# ZEROCROSS_ATmega328.net
KiCad netlist of a schematic drawn in EAGLE
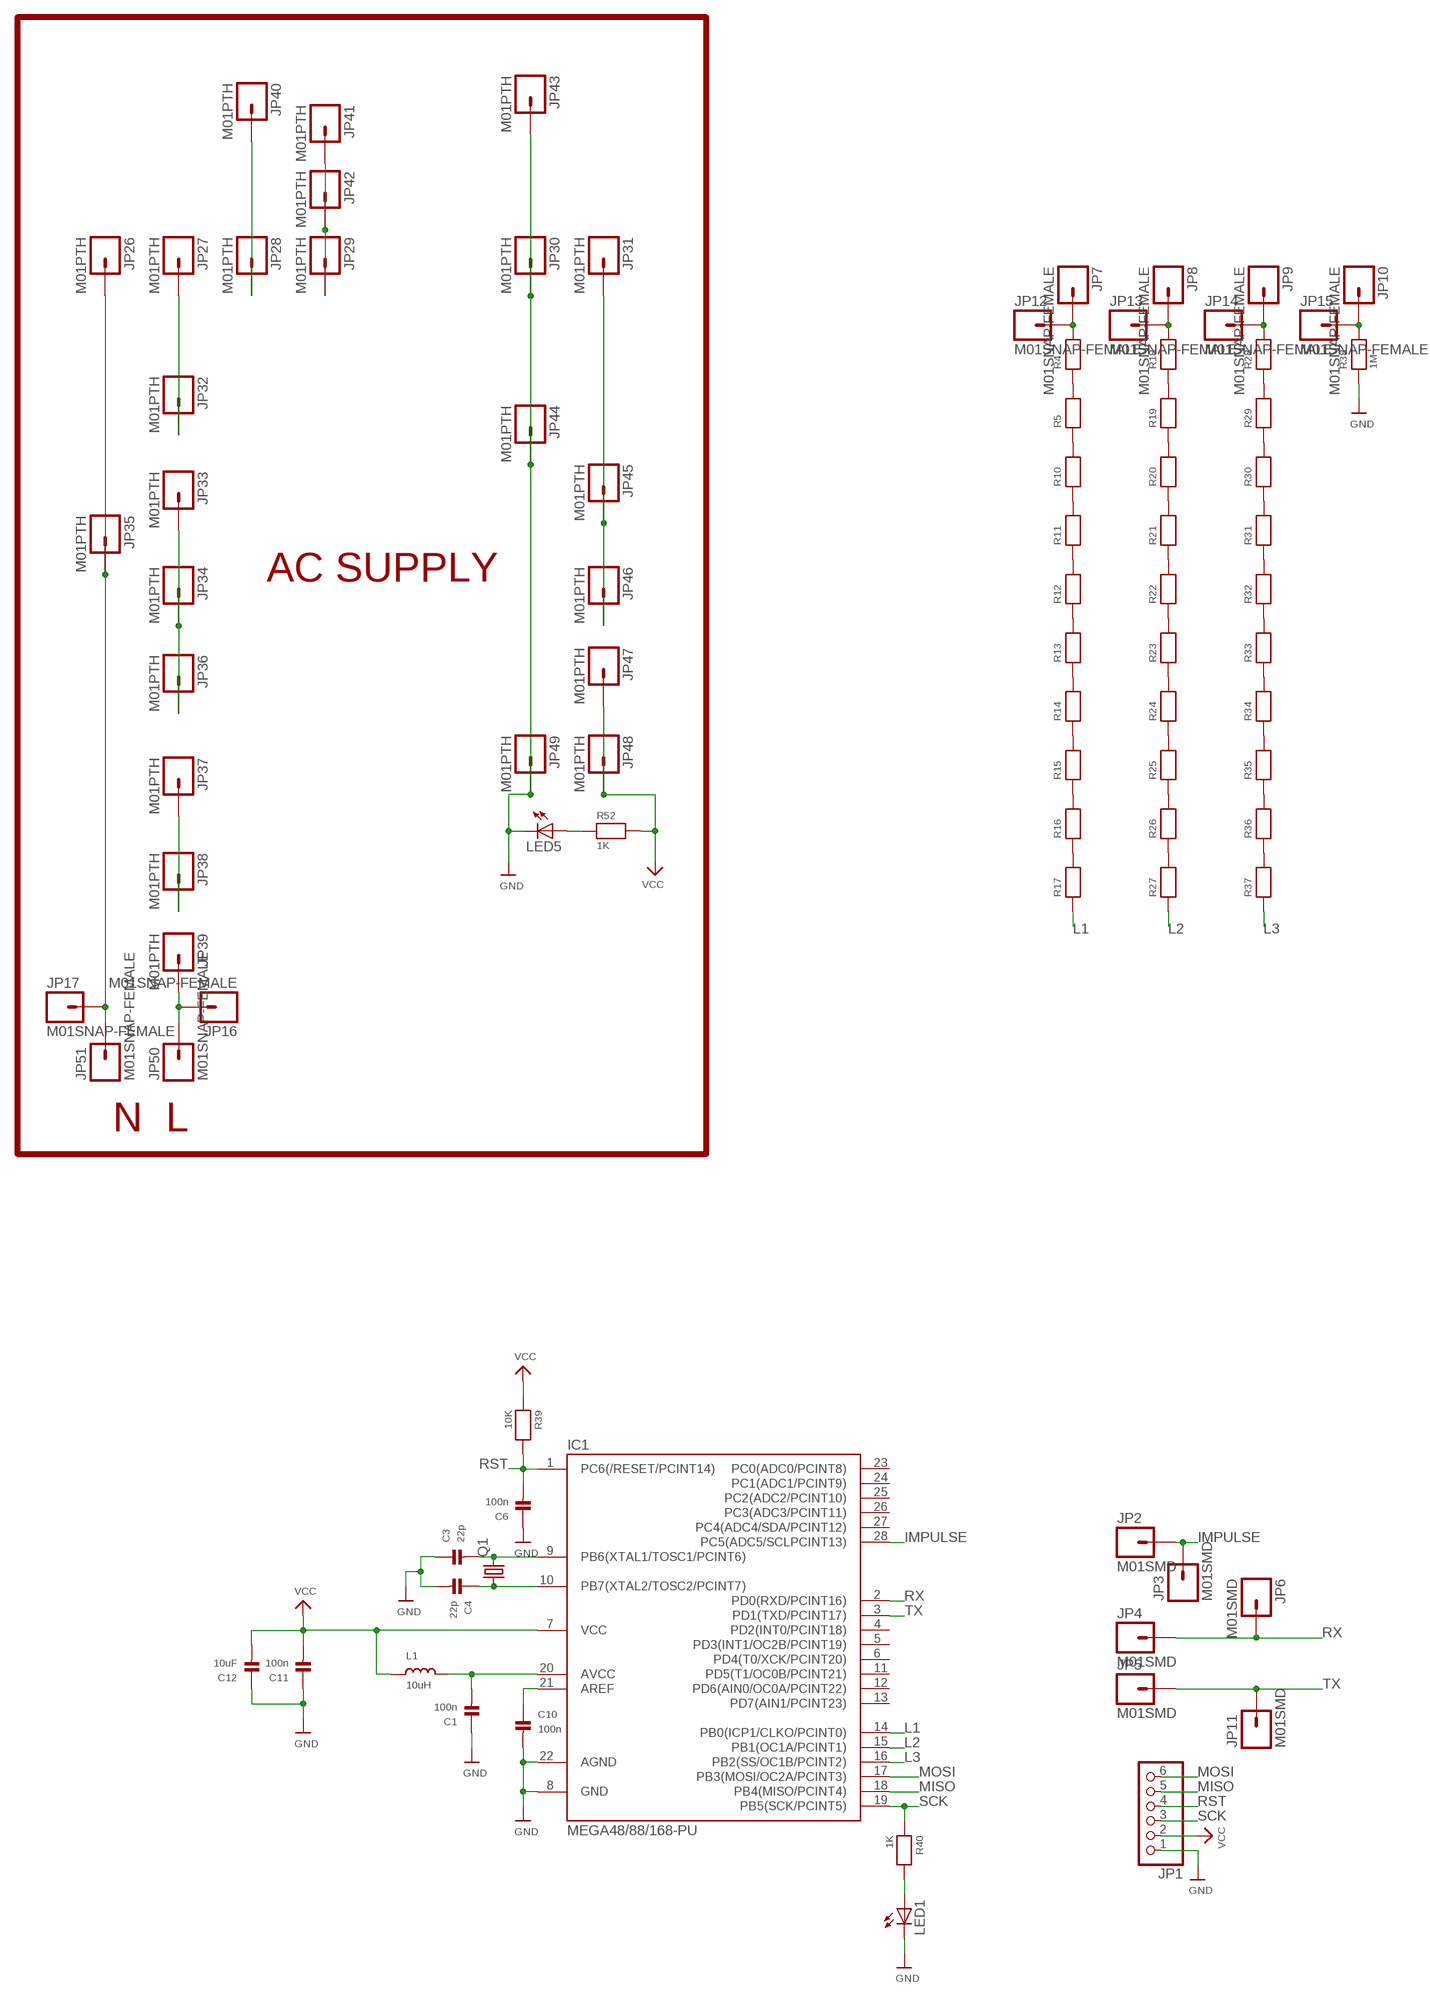
[diagram p0: schematic, sheet 1]

(export (version "E")
  (design (tool "Eeschema 10.0.6"))
  (components
    (comp (ref "C1")
      (value "100n")
      (footprint "eagle-import:_0805MP")
      (libsource (lib "eagle-import") (part "CAP_CERAMIC_0805MP"))
    )
    (comp (ref "C3")
      (value "22p")
      (footprint "eagle-import:_0805MP")
      (libsource (lib "eagle-import") (part "CAP_CERAMIC_0805MP"))
    )
    (comp (ref "C4")
      (value "22p")
      (footprint "eagle-import:_0805MP")
      (libsource (lib "eagle-import") (part "CAP_CERAMIC_0805MP"))
    )
    (comp (ref "C6")
      (value "100n")
      (footprint "eagle-import:_0805MP")
      (libsource (lib "eagle-import") (part "CAP_CERAMIC_0805MP"))
    )
    (comp (ref "C10")
      (value "100n")
      (footprint "eagle-import:_0805MP")
      (libsource (lib "eagle-import") (part "CAP_CERAMIC_0805MP"))
    )
    (comp (ref "C11")
      (value "100n")
      (footprint "eagle-import:_0805MP")
      (libsource (lib "eagle-import") (part "CAP_CERAMIC_0805MP"))
    )
    (comp (ref "C12")
      (value "10uF")
      (footprint "eagle-import:_0805MP")
      (libsource (lib "eagle-import") (part "CAP_CERAMIC_0805MP"))
    )
    (comp (ref "IC1")
      (value "MEGA48/88/168-PU")
      (footprint "eagle-import:DIL28-3")
      (libsource (lib "eagle-import") (part "MEGA48/88/168-PU"))
    )
    (comp (ref "JP1")
      (value "HEADER-1X6")
      (footprint "eagle-import:1X06_OVAL")
      (libsource (lib "eagle-import") (part "HEADER-1X6"))
    )
    (comp (ref "JP2")
      (value "M01SMD")
      (footprint "eagle-import:LUXEON-PAD")
      (libsource (lib "eagle-import") (part "M01SMD"))
    )
    (comp (ref "JP3")
      (value "M01SMD")
      (footprint "eagle-import:LUXEON-PAD")
      (libsource (lib "eagle-import") (part "M01SMD"))
    )
    (comp (ref "JP4")
      (value "M01SMD")
      (footprint "eagle-import:LUXEON-PAD")
      (libsource (lib "eagle-import") (part "M01SMD"))
    )
    (comp (ref "JP5")
      (value "M01SMD")
      (footprint "eagle-import:LUXEON-PAD")
      (libsource (lib "eagle-import") (part "M01SMD"))
    )
    (comp (ref "JP6")
      (value "M01SMD")
      (footprint "eagle-import:LUXEON-PAD")
      (libsource (lib "eagle-import") (part "M01SMD"))
    )
    (comp (ref "JP7")
      (value "M01SNAP-FEMALE")
      (footprint "eagle-import:SNAP-FEMALE")
      (libsource (lib "eagle-import") (part "M01SNAP-FEMALE"))
    )
    (comp (ref "JP8")
      (value "M01SNAP-FEMALE")
      (footprint "eagle-import:SNAP-FEMALE")
      (libsource (lib "eagle-import") (part "M01SNAP-FEMALE"))
    )
    (comp (ref "JP9")
      (value "M01SNAP-FEMALE")
      (footprint "eagle-import:SNAP-FEMALE")
      (libsource (lib "eagle-import") (part "M01SNAP-FEMALE"))
    )
    (comp (ref "JP10")
      (value "M01SNAP-FEMALE")
      (footprint "eagle-import:SNAP-FEMALE")
      (libsource (lib "eagle-import") (part "M01SNAP-FEMALE"))
    )
    (comp (ref "JP11")
      (value "M01SMD")
      (footprint "eagle-import:LUXEON-PAD")
      (libsource (lib "eagle-import") (part "M01SMD"))
    )
    (comp (ref "JP12")
      (value "M01SNAP-FEMALE")
      (footprint "eagle-import:SNAP-FEMALE")
      (libsource (lib "eagle-import") (part "M01SNAP-FEMALE"))
    )
    (comp (ref "JP13")
      (value "M01SNAP-FEMALE")
      (footprint "eagle-import:SNAP-FEMALE")
      (libsource (lib "eagle-import") (part "M01SNAP-FEMALE"))
    )
    (comp (ref "JP14")
      (value "M01SNAP-FEMALE")
      (footprint "eagle-import:SNAP-FEMALE")
      (libsource (lib "eagle-import") (part "M01SNAP-FEMALE"))
    )
    (comp (ref "JP15")
      (value "M01SNAP-FEMALE")
      (footprint "eagle-import:SNAP-FEMALE")
      (libsource (lib "eagle-import") (part "M01SNAP-FEMALE"))
    )
    (comp (ref "JP16")
      (value "M01SNAP-FEMALE")
      (footprint "eagle-import:SNAP-FEMALE")
      (libsource (lib "eagle-import") (part "M01SNAP-FEMALE"))
    )
    (comp (ref "JP17")
      (value "M01SNAP-FEMALE")
      (footprint "eagle-import:SNAP-FEMALE")
      (libsource (lib "eagle-import") (part "M01SNAP-FEMALE"))
    )
    (comp (ref "JP26")
      (value "M01PTH")
      (footprint "eagle-import:1X01")
      (libsource (lib "eagle-import") (part "M01PTH"))
    )
    (comp (ref "JP27")
      (value "M01PTH")
      (footprint "eagle-import:1X01")
      (libsource (lib "eagle-import") (part "M01PTH"))
    )
    (comp (ref "JP28")
      (value "M01PTH")
      (footprint "eagle-import:1X01")
      (libsource (lib "eagle-import") (part "M01PTH"))
    )
    (comp (ref "JP29")
      (value "M01PTH")
      (footprint "eagle-import:1X01")
      (libsource (lib "eagle-import") (part "M01PTH"))
    )
    (comp (ref "JP30")
      (value "M01PTH")
      (footprint "eagle-import:1X01")
      (libsource (lib "eagle-import") (part "M01PTH"))
    )
    (comp (ref "JP31")
      (value "M01PTH")
      (footprint "eagle-import:1X01")
      (libsource (lib "eagle-import") (part "M01PTH"))
    )
    (comp (ref "JP32")
      (value "M01PTH")
      (footprint "eagle-import:1X01")
      (libsource (lib "eagle-import") (part "M01PTH"))
    )
    (comp (ref "JP33")
      (value "M01PTH")
      (footprint "eagle-import:1X01")
      (libsource (lib "eagle-import") (part "M01PTH"))
    )
    (comp (ref "JP34")
      (value "M01PTH")
      (footprint "eagle-import:1X01")
      (libsource (lib "eagle-import") (part "M01PTH"))
    )
    (comp (ref "JP35")
      (value "M01PTH")
      (footprint "eagle-import:1X01")
      (libsource (lib "eagle-import") (part "M01PTH"))
    )
    (comp (ref "JP36")
      (value "M01PTH")
      (footprint "eagle-import:1X01")
      (libsource (lib "eagle-import") (part "M01PTH"))
    )
    (comp (ref "JP37")
      (value "M01PTH")
      (footprint "eagle-import:1X01")
      (libsource (lib "eagle-import") (part "M01PTH"))
    )
    (comp (ref "JP38")
      (value "M01PTH")
      (footprint "eagle-import:1X01")
      (libsource (lib "eagle-import") (part "M01PTH"))
    )
    (comp (ref "JP39")
      (value "M01PTH")
      (footprint "eagle-import:1X01")
      (libsource (lib "eagle-import") (part "M01PTH"))
    )
    (comp (ref "JP40")
      (value "M01PTH")
      (footprint "eagle-import:1X01")
      (libsource (lib "eagle-import") (part "M01PTH"))
    )
    (comp (ref "JP41")
      (value "M01PTH")
      (footprint "eagle-import:1X01")
      (libsource (lib "eagle-import") (part "M01PTH"))
    )
    (comp (ref "JP42")
      (value "M01PTH")
      (footprint "eagle-import:1X01")
      (libsource (lib "eagle-import") (part "M01PTH"))
    )
    (comp (ref "JP43")
      (value "M01PTH")
      (footprint "eagle-import:1X01")
      (libsource (lib "eagle-import") (part "M01PTH"))
    )
    (comp (ref "JP44")
      (value "M01PTH")
      (footprint "eagle-import:1X01")
      (libsource (lib "eagle-import") (part "M01PTH"))
    )
    (comp (ref "JP45")
      (value "M01PTH")
      (footprint "eagle-import:1X01")
      (libsource (lib "eagle-import") (part "M01PTH"))
    )
    (comp (ref "JP46")
      (value "M01PTH")
      (footprint "eagle-import:1X01")
      (libsource (lib "eagle-import") (part "M01PTH"))
    )
    (comp (ref "JP47")
      (value "M01PTH")
      (footprint "eagle-import:1X01")
      (libsource (lib "eagle-import") (part "M01PTH"))
    )
    (comp (ref "JP48")
      (value "M01PTH")
      (footprint "eagle-import:1X01")
      (libsource (lib "eagle-import") (part "M01PTH"))
    )
    (comp (ref "JP49")
      (value "M01PTH")
      (footprint "eagle-import:1X01")
      (libsource (lib "eagle-import") (part "M01PTH"))
    )
    (comp (ref "JP50")
      (value "M01SNAP-FEMALE")
      (footprint "eagle-import:SNAP-FEMALE")
      (libsource (lib "eagle-import") (part "M01SNAP-FEMALE"))
    )
    (comp (ref "JP51")
      (value "M01SNAP-FEMALE")
      (footprint "eagle-import:SNAP-FEMALE")
      (libsource (lib "eagle-import") (part "M01SNAP-FEMALE"))
    )
    (comp (ref "L1")
      (value "10uH")
      (footprint "eagle-import:_0805MP")
      (libsource (lib "eagle-import") (part "INDUCTOR_0805MP"))
    )
    (comp (ref "LED1")
      (value "LED-3MM-NO_SILK")
      (footprint "eagle-import:LED3MM-NS")
      (libsource (lib "eagle-import") (part "LED-3MM-NO_SILK"))
    )
    (comp (ref "LED5")
      (value "LED-3MM-NO_SILK")
      (footprint "eagle-import:LED3MM-NS")
      (libsource (lib "eagle-import") (part "LED-3MM-NO_SILK"))
    )
    (comp (ref "Q1")
      (value "CRYSTALHC49U-V")
      (footprint "eagle-import:HC49U-V")
      (libsource (lib "eagle-import") (part "CRYSTALHC49U-V"))
    )
    (comp (ref "R4")
      (value "RESISTOR1206")
      (footprint "eagle-import:1206")
      (libsource (lib "eagle-import") (part "RESISTOR1206"))
    )
    (comp (ref "R5")
      (value "RESISTOR1206")
      (footprint "eagle-import:1206")
      (libsource (lib "eagle-import") (part "RESISTOR1206"))
    )
    (comp (ref "R10")
      (value "RESISTOR1206")
      (footprint "eagle-import:1206")
      (libsource (lib "eagle-import") (part "RESISTOR1206"))
    )
    (comp (ref "R11")
      (value "RESISTOR1206")
      (footprint "eagle-import:1206")
      (libsource (lib "eagle-import") (part "RESISTOR1206"))
    )
    (comp (ref "R12")
      (value "RESISTOR1206")
      (footprint "eagle-import:1206")
      (libsource (lib "eagle-import") (part "RESISTOR1206"))
    )
    (comp (ref "R13")
      (value "RESISTOR1206")
      (footprint "eagle-import:1206")
      (libsource (lib "eagle-import") (part "RESISTOR1206"))
    )
    (comp (ref "R14")
      (value "RESISTOR1206")
      (footprint "eagle-import:1206")
      (libsource (lib "eagle-import") (part "RESISTOR1206"))
    )
    (comp (ref "R15")
      (value "RESISTOR1206")
      (footprint "eagle-import:1206")
      (libsource (lib "eagle-import") (part "RESISTOR1206"))
    )
    (comp (ref "R16")
      (value "RESISTOR1206")
      (footprint "eagle-import:1206")
      (libsource (lib "eagle-import") (part "RESISTOR1206"))
    )
    (comp (ref "R17")
      (value "RESISTOR1206")
      (footprint "eagle-import:1206")
      (libsource (lib "eagle-import") (part "RESISTOR1206"))
    )
    (comp (ref "R18")
      (value "RESISTOR1206")
      (footprint "eagle-import:1206")
      (libsource (lib "eagle-import") (part "RESISTOR1206"))
    )
    (comp (ref "R19")
      (value "RESISTOR1206")
      (footprint "eagle-import:1206")
      (libsource (lib "eagle-import") (part "RESISTOR1206"))
    )
    (comp (ref "R20")
      (value "RESISTOR1206")
      (footprint "eagle-import:1206")
      (libsource (lib "eagle-import") (part "RESISTOR1206"))
    )
    (comp (ref "R21")
      (value "RESISTOR1206")
      (footprint "eagle-import:1206")
      (libsource (lib "eagle-import") (part "RESISTOR1206"))
    )
    (comp (ref "R22")
      (value "RESISTOR1206")
      (footprint "eagle-import:1206")
      (libsource (lib "eagle-import") (part "RESISTOR1206"))
    )
    (comp (ref "R23")
      (value "RESISTOR1206")
      (footprint "eagle-import:1206")
      (libsource (lib "eagle-import") (part "RESISTOR1206"))
    )
    (comp (ref "R24")
      (value "RESISTOR1206")
      (footprint "eagle-import:1206")
      (libsource (lib "eagle-import") (part "RESISTOR1206"))
    )
    (comp (ref "R25")
      (value "RESISTOR1206")
      (footprint "eagle-import:1206")
      (libsource (lib "eagle-import") (part "RESISTOR1206"))
    )
    (comp (ref "R26")
      (value "RESISTOR1206")
      (footprint "eagle-import:1206")
      (libsource (lib "eagle-import") (part "RESISTOR1206"))
    )
    (comp (ref "R27")
      (value "RESISTOR1206")
      (footprint "eagle-import:1206")
      (libsource (lib "eagle-import") (part "RESISTOR1206"))
    )
    (comp (ref "R28")
      (value "RESISTOR1206")
      (footprint "eagle-import:1206")
      (libsource (lib "eagle-import") (part "RESISTOR1206"))
    )
    (comp (ref "R29")
      (value "RESISTOR1206")
      (footprint "eagle-import:1206")
      (libsource (lib "eagle-import") (part "RESISTOR1206"))
    )
    (comp (ref "R30")
      (value "RESISTOR1206")
      (footprint "eagle-import:1206")
      (libsource (lib "eagle-import") (part "RESISTOR1206"))
    )
    (comp (ref "R31")
      (value "RESISTOR1206")
      (footprint "eagle-import:1206")
      (libsource (lib "eagle-import") (part "RESISTOR1206"))
    )
    (comp (ref "R32")
      (value "RESISTOR1206")
      (footprint "eagle-import:1206")
      (libsource (lib "eagle-import") (part "RESISTOR1206"))
    )
    (comp (ref "R33")
      (value "RESISTOR1206")
      (footprint "eagle-import:1206")
      (libsource (lib "eagle-import") (part "RESISTOR1206"))
    )
    (comp (ref "R34")
      (value "RESISTOR1206")
      (footprint "eagle-import:1206")
      (libsource (lib "eagle-import") (part "RESISTOR1206"))
    )
    (comp (ref "R35")
      (value "RESISTOR1206")
      (footprint "eagle-import:1206")
      (libsource (lib "eagle-import") (part "RESISTOR1206"))
    )
    (comp (ref "R36")
      (value "RESISTOR1206")
      (footprint "eagle-import:1206")
      (libsource (lib "eagle-import") (part "RESISTOR1206"))
    )
    (comp (ref "R37")
      (value "RESISTOR1206")
      (footprint "eagle-import:1206")
      (libsource (lib "eagle-import") (part "RESISTOR1206"))
    )
    (comp (ref "R38")
      (value "1M")
      (footprint "eagle-import:1206")
      (libsource (lib "eagle-import") (part "RESISTOR1206"))
    )
    (comp (ref "R39")
      (value "10K")
      (footprint "eagle-import:_0805MP")
      (libsource (lib "eagle-import") (part "RESISTOR_0805MP"))
    )
    (comp (ref "R40")
      (value "1K")
      (footprint "eagle-import:_0805MP")
      (libsource (lib "eagle-import") (part "RESISTOR_0805MP"))
    )
    (comp (ref "R52")
      (value "1K")
      (footprint "eagle-import:_0805MP")
      (libsource (lib "eagle-import") (part "RESISTOR_0805MP"))
    )
  )
  (nets
    (net (code "1") (name "/IMPULSE") (class "Default")
      (node (ref "IC1") (pin "28") (pinfunction "PC5(ADC5/SCLPCINT13)_28") (pintype "bidirectional"))
      (node (ref "JP2") (pin "P$1") (pinfunction "1_P$1") (pintype "passive"))
      (node (ref "JP3") (pin "P$1") (pinfunction "1_P$1") (pintype "passive"))
    )
    (net (code "2") (name "/L1") (class "Default")
      (node (ref "IC1") (pin "14") (pinfunction "PB0(ICP1/CLKO/PCINT0)_14") (pintype "bidirectional"))
      (node (ref "R17") (pin "1") (pinfunction "1_1") (pintype "passive"))
    )
    (net (code "3") (name "/L2") (class "Default")
      (node (ref "IC1") (pin "15") (pinfunction "PB1(OC1A/PCINT1)_15") (pintype "bidirectional"))
      (node (ref "R27") (pin "1") (pinfunction "1_1") (pintype "passive"))
    )
    (net (code "4") (name "/L3") (class "Default")
      (node (ref "IC1") (pin "16") (pinfunction "PB2(SS/OC1B/PCINT2)_16") (pintype "bidirectional"))
      (node (ref "R37") (pin "1") (pinfunction "1_1") (pintype "passive"))
    )
    (net (code "5") (name "/MISO") (class "Default")
      (node (ref "IC1") (pin "18") (pinfunction "PB4(MISO/PCINT4)_18") (pintype "bidirectional"))
      (node (ref "JP1") (pin "5") (pinfunction "5_5") (pintype "passive"))
    )
    (net (code "6") (name "/MOSI") (class "Default")
      (node (ref "IC1") (pin "17") (pinfunction "PB3(MOSI/OC2A/PCINT3)_17") (pintype "bidirectional"))
      (node (ref "JP1") (pin "6") (pinfunction "6_6") (pintype "passive"))
    )
    (net (code "7") (name "/RST") (class "Default")
      (node (ref "C6") (pin "2") (pinfunction "P$2_2") (pintype "passive"))
      (node (ref "IC1") (pin "1") (pinfunction "PC6(/RESET/PCINT14)_1") (pintype "bidirectional"))
      (node (ref "JP1") (pin "4") (pinfunction "4_4") (pintype "passive"))
      (node (ref "R39") (pin "2") (pinfunction "2_2") (pintype "passive"))
    )
    (net (code "8") (name "/RX") (class "Default")
      (node (ref "IC1") (pin "2") (pinfunction "PD0(RXD/PCINT16)_2") (pintype "bidirectional"))
      (node (ref "JP4") (pin "P$1") (pinfunction "1_P$1") (pintype "passive"))
      (node (ref "JP6") (pin "P$1") (pinfunction "1_P$1") (pintype "passive"))
    )
    (net (code "9") (name "/SCK") (class "Default")
      (node (ref "IC1") (pin "19") (pinfunction "PB5(SCK/PCINT5)_19") (pintype "bidirectional"))
      (node (ref "JP1") (pin "3") (pinfunction "3_3") (pintype "passive"))
      (node (ref "R40") (pin "1") (pinfunction "1_1") (pintype "passive"))
    )
    (net (code "10") (name "/TX") (class "Default")
      (node (ref "IC1") (pin "3") (pinfunction "PD1(TXD/PCINT17)_3") (pintype "bidirectional"))
      (node (ref "JP11") (pin "P$1") (pinfunction "1_P$1") (pintype "passive"))
      (node (ref "JP5") (pin "P$1") (pinfunction "1_P$1") (pintype "passive"))
    )
    (net (code "11") (name "GND") (class "Default")
      (node (ref "C1") (pin "1") (pinfunction "P$1_1") (pintype "passive"))
      (node (ref "C10") (pin "2") (pinfunction "P$2_2") (pintype "passive"))
      (node (ref "C11") (pin "1") (pinfunction "P$1_1") (pintype "passive"))
      (node (ref "C12") (pin "1") (pinfunction "P$1_1") (pintype "passive"))
      (node (ref "C3") (pin "1") (pinfunction "P$1_1") (pintype "passive"))
      (node (ref "C4") (pin "2") (pinfunction "P$2_2") (pintype "passive"))
      (node (ref "C6") (pin "1") (pinfunction "P$1_1") (pintype "passive"))
      (node (ref "IC1") (pin "22") (pinfunction "AGND_22") (pintype "power_in"))
      (node (ref "IC1") (pin "8") (pinfunction "GND_8") (pintype "power_in"))
      (node (ref "JP1") (pin "1") (pinfunction "1_1") (pintype "passive"))
      (node (ref "JP30") (pin "1") (pinfunction "1_1") (pintype "passive"))
      (node (ref "JP43") (pin "1") (pinfunction "1_1") (pintype "passive"))
      (node (ref "JP44") (pin "1") (pinfunction "1_1") (pintype "passive"))
      (node (ref "JP49") (pin "1") (pinfunction "1_1") (pintype "passive"))
      (node (ref "LED1") (pin "K") (pinfunction "C_K") (pintype "passive"))
      (node (ref "LED5") (pin "K") (pinfunction "C_K") (pintype "passive"))
      (node (ref "R38") (pin "1") (pinfunction "1_1") (pintype "passive"))
    )
    (net (code "12") (name "Net-(C1-P$2)") (class "Default")
      (node (ref "C1") (pin "2") (pinfunction "P$2_2") (pintype "passive"))
      (node (ref "IC1") (pin "20") (pinfunction "AVCC_20") (pintype "passive"))
      (node (ref "L1") (pin "2") (pinfunction "2_2") (pintype "passive"))
    )
    (net (code "13") (name "Net-(C3-P$2)") (class "Default")
      (node (ref "C3") (pin "2") (pinfunction "P$2_2") (pintype "passive"))
      (node (ref "IC1") (pin "9") (pinfunction "PB6(XTAL1/TOSC1/PCINT6)_9") (pintype "bidirectional"))
      (node (ref "Q1") (pin "2") (pinfunction "2_2") (pintype "passive"))
    )
    (net (code "14") (name "Net-(C4-P$1)") (class "Default")
      (node (ref "C4") (pin "1") (pinfunction "P$1_1") (pintype "passive"))
      (node (ref "IC1") (pin "10") (pinfunction "PB7(XTAL2/TOSC2/PCINT7)_10") (pintype "bidirectional"))
      (node (ref "Q1") (pin "1") (pinfunction "1_1") (pintype "passive"))
    )
    (net (code "15") (name "Net-(C10-P$1)") (class "Default")
      (node (ref "C10") (pin "1") (pinfunction "P$1_1") (pintype "passive"))
      (node (ref "IC1") (pin "21") (pinfunction "AREF_21") (pintype "passive"))
    )
    (net (code "16") (name "Net-(JP10-Pad1)") (class "Default")
      (node (ref "JP10") (pin "1") (pinfunction "1_1") (pintype "passive"))
      (node (ref "JP15") (pin "1") (pinfunction "1_1") (pintype "passive"))
      (node (ref "R38") (pin "2") (pinfunction "2_2") (pintype "passive"))
    )
    (net (code "17") (name "Net-(JP12-Pad1)") (class "Default")
      (node (ref "JP12") (pin "1") (pinfunction "1_1") (pintype "passive"))
      (node (ref "JP7") (pin "1") (pinfunction "1_1") (pintype "passive"))
      (node (ref "R4") (pin "2") (pinfunction "2_2") (pintype "passive"))
    )
    (net (code "18") (name "Net-(JP13-Pad1)") (class "Default")
      (node (ref "JP13") (pin "1") (pinfunction "1_1") (pintype "passive"))
      (node (ref "JP8") (pin "1") (pinfunction "1_1") (pintype "passive"))
      (node (ref "R18") (pin "2") (pinfunction "2_2") (pintype "passive"))
    )
    (net (code "19") (name "Net-(JP14-Pad1)") (class "Default")
      (node (ref "JP14") (pin "1") (pinfunction "1_1") (pintype "passive"))
      (node (ref "JP9") (pin "1") (pinfunction "1_1") (pintype "passive"))
      (node (ref "R28") (pin "2") (pinfunction "2_2") (pintype "passive"))
    )
    (net (code "20") (name "Net-(JP16-Pad1)") (class "Default")
      (node (ref "JP16") (pin "1") (pinfunction "1_1") (pintype "passive"))
      (node (ref "JP39") (pin "1") (pinfunction "1_1") (pintype "passive"))
      (node (ref "JP50") (pin "1") (pinfunction "1_1") (pintype "passive"))
    )
    (net (code "21") (name "Net-(JP17-Pad1)") (class "Default")
      (node (ref "JP17") (pin "1") (pinfunction "1_1") (pintype "passive"))
      (node (ref "JP26") (pin "1") (pinfunction "1_1") (pintype "passive"))
      (node (ref "JP35") (pin "1") (pinfunction "1_1") (pintype "passive"))
      (node (ref "JP51") (pin "1") (pinfunction "1_1") (pintype "passive"))
    )
    (net (code "22") (name "Net-(JP27-Pad1)") (class "Default")
      (node (ref "JP27") (pin "1") (pinfunction "1_1") (pintype "passive"))
      (node (ref "JP32") (pin "1") (pinfunction "1_1") (pintype "passive"))
    )
    (net (code "23") (name "Net-(JP28-Pad1)") (class "Default")
      (node (ref "JP28") (pin "1") (pinfunction "1_1") (pintype "passive"))
      (node (ref "JP40") (pin "1") (pinfunction "1_1") (pintype "passive"))
    )
    (net (code "24") (name "Net-(JP29-Pad1)") (class "Default")
      (node (ref "JP29") (pin "1") (pinfunction "1_1") (pintype "passive"))
      (node (ref "JP41") (pin "1") (pinfunction "1_1") (pintype "passive"))
      (node (ref "JP42") (pin "1") (pinfunction "1_1") (pintype "passive"))
    )
    (net (code "25") (name "Net-(JP31-Pad1)") (class "Default")
      (node (ref "JP31") (pin "1") (pinfunction "1_1") (pintype "passive"))
      (node (ref "JP45") (pin "1") (pinfunction "1_1") (pintype "passive"))
      (node (ref "JP46") (pin "1") (pinfunction "1_1") (pintype "passive"))
    )
    (net (code "26") (name "Net-(JP33-Pad1)") (class "Default")
      (node (ref "JP33") (pin "1") (pinfunction "1_1") (pintype "passive"))
      (node (ref "JP34") (pin "1") (pinfunction "1_1") (pintype "passive"))
      (node (ref "JP36") (pin "1") (pinfunction "1_1") (pintype "passive"))
    )
    (net (code "27") (name "Net-(JP37-Pad1)") (class "Default")
      (node (ref "JP37") (pin "1") (pinfunction "1_1") (pintype "passive"))
      (node (ref "JP38") (pin "1") (pinfunction "1_1") (pintype "passive"))
    )
    (net (code "28") (name "Net-(LED1-PadA)") (class "Default")
      (node (ref "LED1") (pin "A") (pinfunction "A_A") (pintype "passive"))
      (node (ref "R40") (pin "2") (pinfunction "2_2") (pintype "passive"))
    )
    (net (code "29") (name "Net-(LED5-PadA)") (class "Default")
      (node (ref "LED5") (pin "A") (pinfunction "A_A") (pintype "passive"))
      (node (ref "R52") (pin "1") (pinfunction "1_1") (pintype "passive"))
    )
    (net (code "30") (name "Net-(R4-Pad1)") (class "Default")
      (node (ref "R4") (pin "1") (pinfunction "1_1") (pintype "passive"))
      (node (ref "R5") (pin "2") (pinfunction "2_2") (pintype "passive"))
    )
    (net (code "31") (name "Net-(R10-Pad1)") (class "Default")
      (node (ref "R10") (pin "1") (pinfunction "1_1") (pintype "passive"))
      (node (ref "R11") (pin "2") (pinfunction "2_2") (pintype "passive"))
    )
    (net (code "32") (name "Net-(R10-Pad2)") (class "Default")
      (node (ref "R10") (pin "2") (pinfunction "2_2") (pintype "passive"))
      (node (ref "R5") (pin "1") (pinfunction "1_1") (pintype "passive"))
    )
    (net (code "33") (name "Net-(R11-Pad1)") (class "Default")
      (node (ref "R11") (pin "1") (pinfunction "1_1") (pintype "passive"))
      (node (ref "R12") (pin "2") (pinfunction "2_2") (pintype "passive"))
    )
    (net (code "34") (name "Net-(R12-Pad1)") (class "Default")
      (node (ref "R12") (pin "1") (pinfunction "1_1") (pintype "passive"))
      (node (ref "R13") (pin "2") (pinfunction "2_2") (pintype "passive"))
    )
    (net (code "35") (name "Net-(R13-Pad1)") (class "Default")
      (node (ref "R13") (pin "1") (pinfunction "1_1") (pintype "passive"))
      (node (ref "R14") (pin "2") (pinfunction "2_2") (pintype "passive"))
    )
    (net (code "36") (name "Net-(R14-Pad1)") (class "Default")
      (node (ref "R14") (pin "1") (pinfunction "1_1") (pintype "passive"))
      (node (ref "R15") (pin "2") (pinfunction "2_2") (pintype "passive"))
    )
    (net (code "37") (name "Net-(R15-Pad1)") (class "Default")
      (node (ref "R15") (pin "1") (pinfunction "1_1") (pintype "passive"))
      (node (ref "R16") (pin "2") (pinfunction "2_2") (pintype "passive"))
    )
    (net (code "38") (name "Net-(R16-Pad1)") (class "Default")
      (node (ref "R16") (pin "1") (pinfunction "1_1") (pintype "passive"))
      (node (ref "R17") (pin "2") (pinfunction "2_2") (pintype "passive"))
    )
    (net (code "39") (name "Net-(R18-Pad1)") (class "Default")
      (node (ref "R18") (pin "1") (pinfunction "1_1") (pintype "passive"))
      (node (ref "R19") (pin "2") (pinfunction "2_2") (pintype "passive"))
    )
    (net (code "40") (name "Net-(R19-Pad1)") (class "Default")
      (node (ref "R19") (pin "1") (pinfunction "1_1") (pintype "passive"))
      (node (ref "R20") (pin "2") (pinfunction "2_2") (pintype "passive"))
    )
    (net (code "41") (name "Net-(R20-Pad1)") (class "Default")
      (node (ref "R20") (pin "1") (pinfunction "1_1") (pintype "passive"))
      (node (ref "R21") (pin "2") (pinfunction "2_2") (pintype "passive"))
    )
    (net (code "42") (name "Net-(R21-Pad1)") (class "Default")
      (node (ref "R21") (pin "1") (pinfunction "1_1") (pintype "passive"))
      (node (ref "R22") (pin "2") (pinfunction "2_2") (pintype "passive"))
    )
    (net (code "43") (name "Net-(R22-Pad1)") (class "Default")
      (node (ref "R22") (pin "1") (pinfunction "1_1") (pintype "passive"))
      (node (ref "R23") (pin "2") (pinfunction "2_2") (pintype "passive"))
    )
    (net (code "44") (name "Net-(R23-Pad1)") (class "Default")
      (node (ref "R23") (pin "1") (pinfunction "1_1") (pintype "passive"))
      (node (ref "R24") (pin "2") (pinfunction "2_2") (pintype "passive"))
    )
    (net (code "45") (name "Net-(R24-Pad1)") (class "Default")
      (node (ref "R24") (pin "1") (pinfunction "1_1") (pintype "passive"))
      (node (ref "R25") (pin "2") (pinfunction "2_2") (pintype "passive"))
    )
    (net (code "46") (name "Net-(R25-Pad1)") (class "Default")
      (node (ref "R25") (pin "1") (pinfunction "1_1") (pintype "passive"))
      (node (ref "R26") (pin "2") (pinfunction "2_2") (pintype "passive"))
    )
    (net (code "47") (name "Net-(R26-Pad1)") (class "Default")
      (node (ref "R26") (pin "1") (pinfunction "1_1") (pintype "passive"))
      (node (ref "R27") (pin "2") (pinfunction "2_2") (pintype "passive"))
    )
    (net (code "48") (name "Net-(R28-Pad1)") (class "Default")
      (node (ref "R28") (pin "1") (pinfunction "1_1") (pintype "passive"))
      (node (ref "R29") (pin "2") (pinfunction "2_2") (pintype "passive"))
    )
    (net (code "49") (name "Net-(R29-Pad1)") (class "Default")
      (node (ref "R29") (pin "1") (pinfunction "1_1") (pintype "passive"))
      (node (ref "R30") (pin "2") (pinfunction "2_2") (pintype "passive"))
    )
    (net (code "50") (name "Net-(R30-Pad1)") (class "Default")
      (node (ref "R30") (pin "1") (pinfunction "1_1") (pintype "passive"))
      (node (ref "R31") (pin "2") (pinfunction "2_2") (pintype "passive"))
    )
    (net (code "51") (name "Net-(R31-Pad1)") (class "Default")
      (node (ref "R31") (pin "1") (pinfunction "1_1") (pintype "passive"))
      (node (ref "R32") (pin "2") (pinfunction "2_2") (pintype "passive"))
    )
    (net (code "52") (name "Net-(R32-Pad1)") (class "Default")
      (node (ref "R32") (pin "1") (pinfunction "1_1") (pintype "passive"))
      (node (ref "R33") (pin "2") (pinfunction "2_2") (pintype "passive"))
    )
    (net (code "53") (name "Net-(R33-Pad1)") (class "Default")
      (node (ref "R33") (pin "1") (pinfunction "1_1") (pintype "passive"))
      (node (ref "R34") (pin "2") (pinfunction "2_2") (pintype "passive"))
    )
    (net (code "54") (name "Net-(R34-Pad1)") (class "Default")
      (node (ref "R34") (pin "1") (pinfunction "1_1") (pintype "passive"))
      (node (ref "R35") (pin "2") (pinfunction "2_2") (pintype "passive"))
    )
    (net (code "55") (name "Net-(R35-Pad1)") (class "Default")
      (node (ref "R35") (pin "1") (pinfunction "1_1") (pintype "passive"))
      (node (ref "R36") (pin "2") (pinfunction "2_2") (pintype "passive"))
    )
    (net (code "56") (name "Net-(R36-Pad1)") (class "Default")
      (node (ref "R36") (pin "1") (pinfunction "1_1") (pintype "passive"))
      (node (ref "R37") (pin "2") (pinfunction "2_2") (pintype "passive"))
    )
    (net (code "57") (name "VCC") (class "Default")
      (node (ref "C11") (pin "2") (pinfunction "P$2_2") (pintype "passive"))
      (node (ref "C12") (pin "2") (pinfunction "P$2_2") (pintype "passive"))
      (node (ref "IC1") (pin "7") (pinfunction "VCC_7") (pintype "power_in"))
      (node (ref "JP1") (pin "2") (pinfunction "2_2") (pintype "passive"))
      (node (ref "JP47") (pin "1") (pinfunction "1_1") (pintype "passive"))
      (node (ref "JP48") (pin "1") (pinfunction "1_1") (pintype "passive"))
      (node (ref "L1") (pin "1") (pinfunction "1_1") (pintype "passive"))
      (node (ref "R39") (pin "1") (pinfunction "1_1") (pintype "passive"))
      (node (ref "R52") (pin "2") (pinfunction "2_2") (pintype "passive"))
    )
    (net (code "58") (name "unconnected-(IC1-PC0(ADC0{slash}PCINT8)-Pad23)") (class "Default")
      (node (ref "IC1") (pin "23") (pinfunction "PC0(ADC0/PCINT8)_23") (pintype "bidirectional"))
    )
    (net (code "59") (name "unconnected-(IC1-PC1(ADC1{slash}PCINT9)-Pad24)") (class "Default")
      (node (ref "IC1") (pin "24") (pinfunction "PC1(ADC1/PCINT9)_24") (pintype "bidirectional"))
    )
    (net (code "60") (name "unconnected-(IC1-PC2(ADC2{slash}PCINT10)-Pad25)") (class "Default")
      (node (ref "IC1") (pin "25") (pinfunction "PC2(ADC2/PCINT10)_25") (pintype "bidirectional"))
    )
    (net (code "61") (name "unconnected-(IC1-PC3(ADC3{slash}PCINT11)-Pad26)") (class "Default")
      (node (ref "IC1") (pin "26") (pinfunction "PC3(ADC3/PCINT11)_26") (pintype "bidirectional"))
    )
    (net (code "62") (name "unconnected-(IC1-PC4(ADC4{slash}SDA{slash}PCINT12)-Pad27)") (class "Default")
      (node (ref "IC1") (pin "27") (pinfunction "PC4(ADC4/SDA/PCINT12)_27") (pintype "bidirectional"))
    )
    (net (code "63") (name "unconnected-(IC1-PD2(INT0{slash}PCINT18)-Pad4)") (class "Default")
      (node (ref "IC1") (pin "4") (pinfunction "PD2(INT0/PCINT18)_4") (pintype "bidirectional"))
    )
    (net (code "64") (name "unconnected-(IC1-PD3(INT1{slash}OC2B{slash}PCINT19)-Pad5)") (class "Default")
      (node (ref "IC1") (pin "5") (pinfunction "PD3(INT1/OC2B/PCINT19)_5") (pintype "bidirectional"))
    )
    (net (code "65") (name "unconnected-(IC1-PD4(T0{slash}XCK{slash}PCINT20)-Pad6)") (class "Default")
      (node (ref "IC1") (pin "6") (pinfunction "PD4(T0/XCK/PCINT20)_6") (pintype "bidirectional"))
    )
    (net (code "66") (name "unconnected-(IC1-PD5(T1{slash}OC0B{slash}PCINT21)-Pad11)") (class "Default")
      (node (ref "IC1") (pin "11") (pinfunction "PD5(T1/OC0B/PCINT21)_11") (pintype "bidirectional"))
    )
    (net (code "67") (name "unconnected-(IC1-PD6(AIN0{slash}OC0A{slash}PCINT22)-Pad12)") (class "Default")
      (node (ref "IC1") (pin "12") (pinfunction "PD6(AIN0/OC0A/PCINT22)_12") (pintype "bidirectional"))
    )
    (net (code "68") (name "unconnected-(IC1-PD7(AIN1{slash}PCINT23)-Pad13)") (class "Default")
      (node (ref "IC1") (pin "13") (pinfunction "PD7(AIN1/PCINT23)_13") (pintype "bidirectional"))
    )
  )
)
